# Schematics.net
KiCad netlist of a schematic drawn in Altium Designer
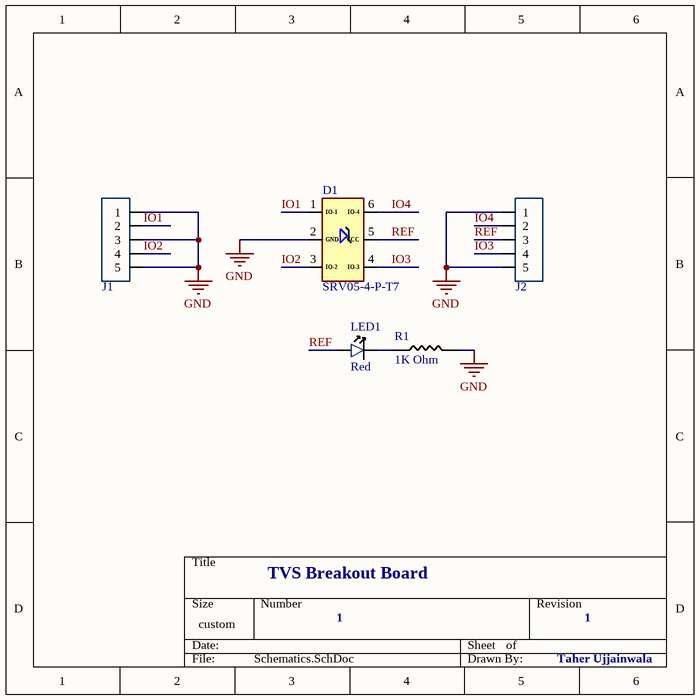
[diagram p0: Schematics.SchDoc]

(export (version "E")
  (design (tool "Eeschema 10.0.6"))
  (components
    (comp (ref "D1")
      (value "SRV05-4-P-T7")
      (footprint "TVS")
      (description "TVS SOT-23-6 ROHS")
      (fields (field (name "LCSC PART#") "C85364"))
      (libsource (lib "ECEN5730Lib_JLC_2021_08") (part "D_TVS_Diode"))
    )
    (comp (ref "J1")
      (value "J_5_PIN_HEADER")
      (footprint "5_PIN_100MIL")
      (description "5 Position Header Connector 0.100\" (2.54mm) Through Hole Tin")
      (libsource (lib "") (part "J_5_PIN_HEADER_1"))
    )
    (comp (ref "J2")
      (value "J_5_PIN_HEADER")
      (footprint "5_PIN_100MIL")
      (description "5 Position Header Connector 0.100\" (2.54mm) Through Hole Tin")
      (libsource (lib "ECEN5730Lib_Manual_2022_07LibPkg") (part "J_5_PIN_HEADER"))
    )
    (comp (ref "LED1")
      (value "Red")
      (footprint "LED_0603")
      (description "LIGHT EMITTING DIODES (LED) RED 520~625NM 90~100MCD@20MA TOP VIEW 0603 ROHS")
      (fields (field (name "MFR PART #") "KT-0603R") (field (name "LCSC PART#") "C2286"))
      (libsource (lib "ECEN5730Lib_JLC_2022_07") (part "LED_RED_0603"))
    )
    (comp (ref "R1")
      (value "1K Ohm")
      (footprint "0402_Passive_Resistor")
      (description "1 kOhms chip resistor SURFACE MOUNT 1KOHMS ±1% 1/16W 0402 ROHS")
      (fields (field (name "MFR PART #") "0402WGF1001TCE") (field (name "LCSC PART#") "C11702"))
      (libsource (lib "ECEN5730Lib_JLC_2022_07") (part "R_1K_0402"))
    )
  )
  (nets
    (net (code "1") (name "/IO1") (class "Default")
      (node (ref "D1") (pin "1") (pinfunction "IO-1_1") (pintype "passive"))
      (node (ref "J1") (pin "2") (pinfunction "2_2") (pintype "passive"))
    )
    (net (code "2") (name "/IO2") (class "Default")
      (node (ref "D1") (pin "3") (pinfunction "IO-2_3") (pintype "passive"))
      (node (ref "J1") (pin "4") (pinfunction "4_4") (pintype "passive"))
    )
    (net (code "3") (name "/IO3") (class "Default")
      (node (ref "D1") (pin "4") (pinfunction "IO-3_4") (pintype "passive"))
      (node (ref "J2") (pin "4") (pinfunction "4_4") (pintype "passive"))
    )
    (net (code "4") (name "/IO4") (class "Default")
      (node (ref "D1") (pin "6") (pinfunction "IO-4_6") (pintype "passive"))
      (node (ref "J2") (pin "2") (pinfunction "2_2") (pintype "passive"))
    )
    (net (code "5") (name "/REF") (class "Default")
      (node (ref "D1") (pin "5") (pinfunction "VCC_5") (pintype "passive"))
      (node (ref "J2") (pin "3") (pinfunction "3_3") (pintype "passive"))
      (node (ref "LED1") (pin "1") (pinfunction "1_1") (pintype "passive"))
    )
    (net (code "6") (name "GND") (class "Default")
      (node (ref "D1") (pin "2") (pinfunction "GND_2") (pintype "passive"))
      (node (ref "J1") (pin "1") (pinfunction "1_1") (pintype "passive"))
      (node (ref "J1") (pin "3") (pinfunction "3_3") (pintype "passive"))
      (node (ref "J1") (pin "5") (pinfunction "5_5") (pintype "passive"))
      (node (ref "J2") (pin "1") (pinfunction "1_1") (pintype "passive"))
      (node (ref "J2") (pin "5") (pinfunction "5_5") (pintype "passive"))
      (node (ref "R1") (pin "2") (pinfunction "2_2") (pintype "passive"))
    )
    (net (code "7") (name "Net-(LED1-Pad2)") (class "Default")
      (node (ref "LED1") (pin "2") (pinfunction "2_2") (pintype "passive"))
      (node (ref "R1") (pin "1") (pinfunction "1_1") (pintype "passive"))
    )
  )
)
